# bob_v2.net
KiCad netlist of a schematic drawn in Altium Designer
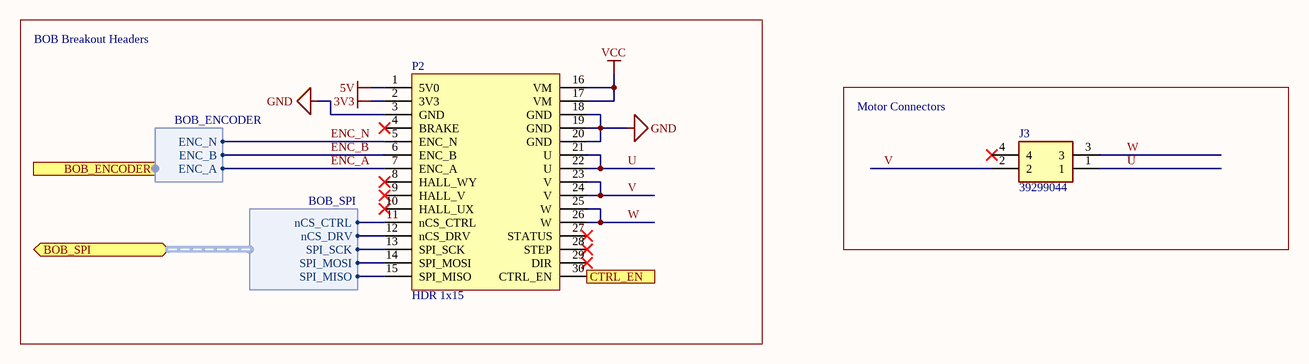
[diagram p0: bob_v2.SchDoc]

(export (version "E")
  (design (tool "Eeschema 10.0.6"))
  (components
    (comp (ref "J3")
      (value "39299044")
      (footprint "39299044")
      (description "Molex 39299044 4POS Minifit\r\ndual row, vertical")
      (libsource (lib "AltiumLibraries") (part "CN HDR 4POS Molex CN HDR 4POS Molex 39299044 VERT"))
    )
    (comp (ref "P2")
      (value "HDR 1x15")
      (footprint "TRINAMIC_BOB")
      (libsource (lib "AltiumLibraries") (part "TRINAMIC_BOB"))
    )
  )
  (nets
    (net (code "3") (name "/CTRL_EN") (class "Default")
      (node (ref "P2") (pin "30") (pinfunction "CTRL_EN_30") (pintype "passive"))
    )
    (net (code "4") (name "/ENC_A") (class "Default")
      (node (ref "P2") (pin "7") (pinfunction "ENC_A_7") (pintype "passive"))
    )
    (net (code "5") (name "/ENC_B") (class "Default")
      (node (ref "P2") (pin "6") (pinfunction "ENC_B_6") (pintype "passive"))
    )
    (net (code "6") (name "/ENC_N") (class "Default")
      (node (ref "P2") (pin "5") (pinfunction "ENC_N_5") (pintype "passive"))
    )
    (net (code "7") (name "/SPI_MISO") (class "Default")
      (node (ref "P2") (pin "15") (pinfunction "SPI_MISO_15") (pintype "passive"))
    )
    (net (code "8") (name "/SPI_MOSI") (class "Default")
      (node (ref "P2") (pin "14") (pinfunction "SPI_MOSI_14") (pintype "passive"))
    )
    (net (code "9") (name "/SPI_SCK") (class "Default")
      (node (ref "P2") (pin "13") (pinfunction "SPI_SCK_13") (pintype "passive"))
    )
    (net (code "10") (name "/U") (class "Default")
      (node (ref "J3") (pin "1") (pinfunction "1_1") (pintype "passive"))
      (node (ref "P2") (pin "21") (pinfunction "U_21") (pintype "passive"))
      (node (ref "P2") (pin "22") (pinfunction "U_22") (pintype "passive"))
    )
    (net (code "11") (name "/V") (class "Default")
      (node (ref "J3") (pin "2") (pinfunction "2_2") (pintype "passive"))
      (node (ref "P2") (pin "23") (pinfunction "V_23") (pintype "passive"))
      (node (ref "P2") (pin "24") (pinfunction "V_24") (pintype "passive"))
    )
    (net (code "12") (name "/W") (class "Default")
      (node (ref "J3") (pin "3") (pinfunction "3_3") (pintype "passive"))
      (node (ref "P2") (pin "25") (pinfunction "W_25") (pintype "passive"))
      (node (ref "P2") (pin "26") (pinfunction "W_26") (pintype "passive"))
    )
    (net (code "13") (name "/nCS_CTRL") (class "Default")
      (node (ref "P2") (pin "11") (pinfunction "nCS_CTRL_11") (pintype "passive"))
    )
    (net (code "14") (name "/nCS_DRV") (class "Default")
      (node (ref "P2") (pin "12") (pinfunction "nCS_DRV_12") (pintype "passive"))
    )
    (net (code "17") (name "3V3") (class "Default")
      (node (ref "P2") (pin "2") (pinfunction "3V3_2") (pintype "passive"))
    )
    (net (code "18") (name "5V") (class "Default")
      (node (ref "P2") (pin "1") (pinfunction "5V0_1") (pintype "passive"))
    )
    (net (code "19") (name "GND") (class "Default")
      (node (ref "P2") (pin "18") (pinfunction "GND_18") (pintype "passive"))
      (node (ref "P2") (pin "19") (pinfunction "GND_19") (pintype "passive"))
      (node (ref "P2") (pin "20") (pinfunction "GND_20") (pintype "passive"))
      (node (ref "P2") (pin "3") (pinfunction "GND_3") (pintype "passive"))
    )
    (net (code "20") (name "VCC") (class "Default")
      (node (ref "P2") (pin "16") (pinfunction "VM_16") (pintype "passive"))
      (node (ref "P2") (pin "17") (pinfunction "VM_17") (pintype "passive"))
    )
    (net (code "21") (name "unconnected-(J3-Pad4)") (class "Default")
      (node (ref "J3") (pin "4") (pinfunction "4_4") (pintype "passive+no_connect"))
    )
    (net (code "22") (name "unconnected-(P2-BRAKE-Pad4)") (class "Default")
      (node (ref "P2") (pin "4") (pinfunction "BRAKE_4") (pintype "passive+no_connect"))
    )
    (net (code "23") (name "unconnected-(P2-DIR-Pad29)") (class "Default")
      (node (ref "P2") (pin "29") (pinfunction "DIR_29") (pintype "passive+no_connect"))
    )
    (net (code "24") (name "unconnected-(P2-HALL_UX-Pad10)") (class "Default")
      (node (ref "P2") (pin "10") (pinfunction "HALL_UX_10") (pintype "passive+no_connect"))
    )
    (net (code "25") (name "unconnected-(P2-HALL_V-Pad9)") (class "Default")
      (node (ref "P2") (pin "9") (pinfunction "HALL_V_9") (pintype "passive+no_connect"))
    )
    (net (code "26") (name "unconnected-(P2-HALL_WY-Pad8)") (class "Default")
      (node (ref "P2") (pin "8") (pinfunction "HALL_WY_8") (pintype "passive+no_connect"))
    )
    (net (code "27") (name "unconnected-(P2-STATUS-Pad27)") (class "Default")
      (node (ref "P2") (pin "27") (pinfunction "STATUS_27") (pintype "passive+no_connect"))
    )
    (net (code "28") (name "unconnected-(P2-STEP-Pad28)") (class "Default")
      (node (ref "P2") (pin "28") (pinfunction "STEP_28") (pintype "passive+no_connect"))
    )
  )
)
